# SCH_AT89.net
KiCad netlist of a schematic drawn in Altium Designer
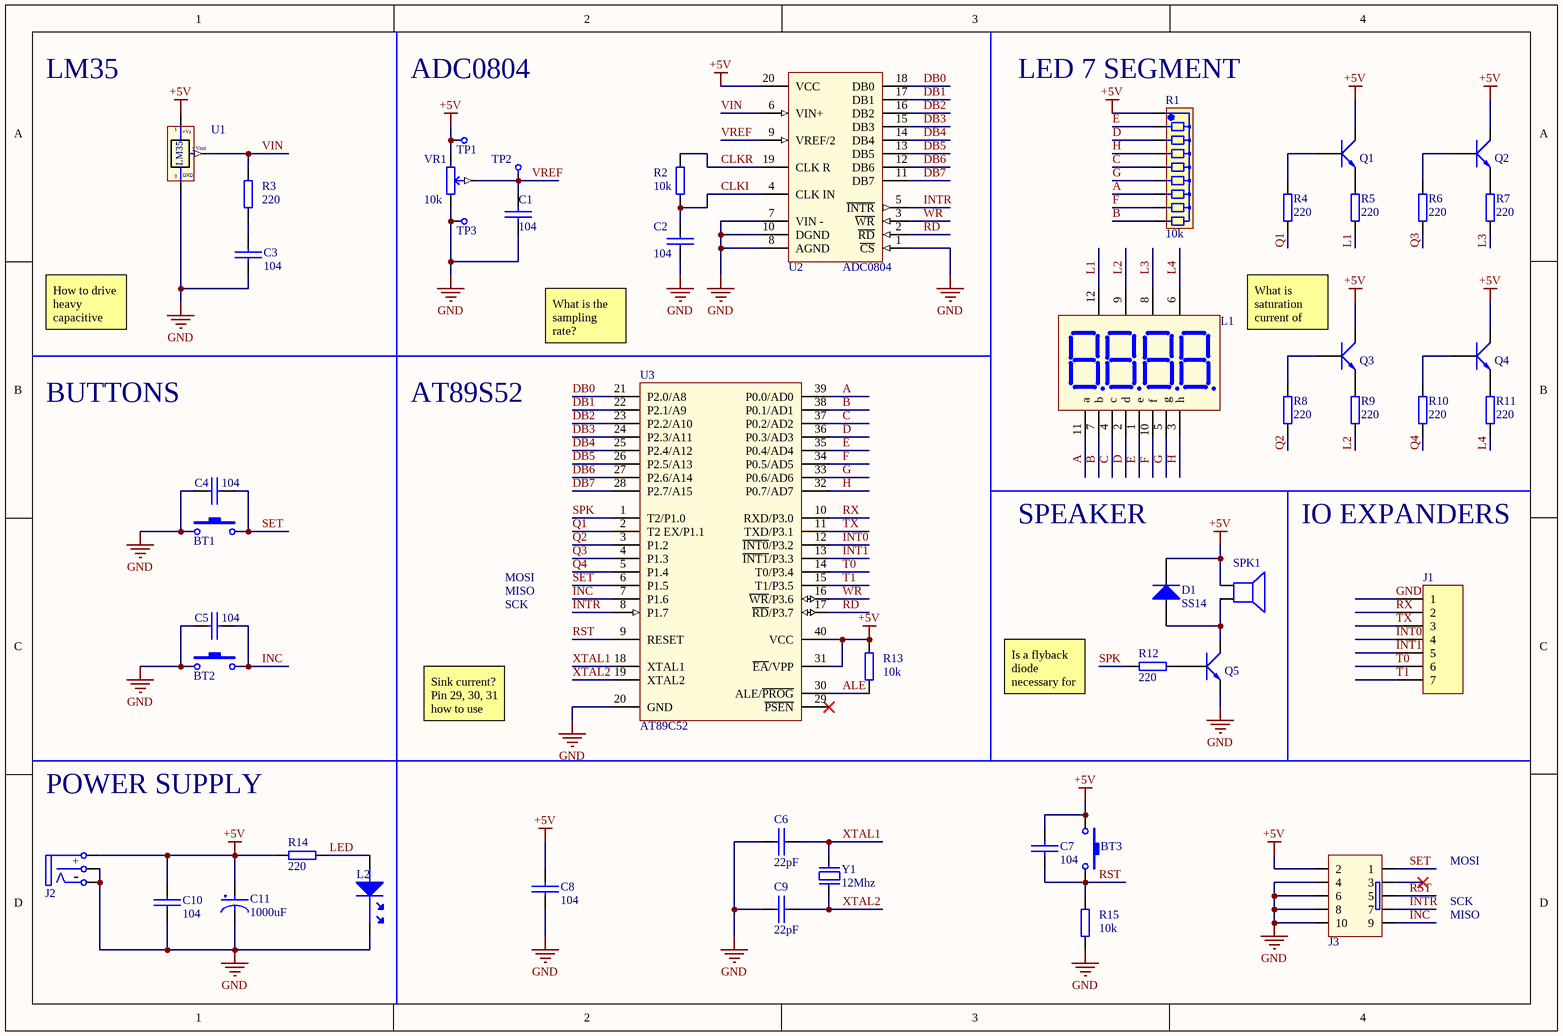
[diagram p0: SCH_AT89.SchDoc]

(export (version "E")
  (design (tool "Eeschema 10.0.6"))
  (components
    (comp (ref "BT1")
      (value "Nut Nhan 2 Chan SMD 3x6x2.5")
      (footprint "Nut Nhan 2 Chan SMD 3x6x2.5")
      (libsource (lib "Altium_Lib_by_KhueNguyenCreator") (part "Nut Nhan 2 Chan SMD 3x6x2.5"))
    )
    (comp (ref "BT2")
      (value "Nut Nhan 2 Chan SMD 3x6x2.5")
      (footprint "Nut Nhan 2 Chan SMD 3x6x2.5")
      (libsource (lib "Altium_Lib_by_KhueNguyenCreator") (part "Nut Nhan 2 Chan SMD 3x6x2.5"))
    )
    (comp (ref "BT3")
      (value "Nut Nhan 2 Chan SMD 3x6x2.5")
      (footprint "Nut Nhan 2 Chan SMD 3x6x2.5")
      (libsource (lib "Altium_Lib_by_KhueNguyenCreator") (part "Nut Nhan 2 Chan SMD 3x6x2.5"))
    )
    (comp (ref "C1")
      (value "104")
      (footprint "tu 0805")
      (description "SMD")
      (libsource (lib "PRJ_AT89") (part "CAP0805"))
    )
    (comp (ref "C2")
      (value "104")
      (footprint "tu 0805")
      (description "SMD")
      (libsource (lib "PRJ_AT89") (part "CAP0805"))
    )
    (comp (ref "C3")
      (value "104")
      (footprint "tu 0805")
      (description "SMD")
      (libsource (lib "PRJ_AT89") (part "CAP0805"))
    )
    (comp (ref "C4")
      (value "104")
      (footprint "tu 0805")
      (description "SMD")
      (libsource (lib "PRJ_AT89") (part "CAP0805"))
    )
    (comp (ref "C5")
      (value "104")
      (footprint "tu 0805")
      (description "SMD")
      (libsource (lib "PRJ_AT89") (part "CAP0805"))
    )
    (comp (ref "C6")
      (value "22pF")
      (footprint "tu 0805")
      (description "SMD")
      (libsource (lib "PRJ_AT89") (part "CAP0805"))
    )
    (comp (ref "C7")
      (value "104")
      (footprint "tu 0805")
      (description "SMD")
      (libsource (lib "PRJ_AT89") (part "CAP0805"))
    )
    (comp (ref "C8")
      (value "104")
      (footprint "tu 0805")
      (description "SMD")
      (libsource (lib "PRJ_AT89") (part "CAP0805"))
    )
    (comp (ref "C9")
      (value "22pF")
      (footprint "tu 0805")
      (description "SMD")
      (libsource (lib "PRJ_AT89") (part "CAP0805"))
    )
    (comp (ref "C10")
      (value "104")
      (footprint "tu 0805")
      (description "SMD")
      (libsource (lib "PRJ_AT89") (part "CAP0805"))
    )
    (comp (ref "C11")
      (value "1000uF")
      (footprint "tu hoa 10mm")
      (description "THT")
      (libsource (lib "PRJ_AT89") (part "CAPElectrolytic"))
    )
    (comp (ref "D1")
      (value "SS14")
      (footprint "DIODE SMA")
      (description "Dán")
      (libsource (lib "Altium_Lib_by_KhueNguyenCreator") (part "Diode SS14 ( 1N5819)"))
    )
    (comp (ref "J1")
      (value "Header 7")
      (footprint "HDR1X7")
      (description "Header, 7-Pin")
      (fields (field (name "PUBLISHER") "Altium Limited"))
      (libsource (lib "Miscellaneous Connectors") (part "Header 7"))
    )
    (comp (ref "J2")
      (value "JACK DC 5.5")
      (footprint "JACK DC 5.5")
      (description "THT")
      (libsource (lib "PRJ_AT89") (part "JACK DC 5.5"))
    )
    (comp (ref "J3")
      (value "IDC 5X2")
      (footprint "IDC10")
      (description "THT")
      (libsource (lib "PRJ_AT89") (part "ICSP 5x2"))
    )
    (comp (ref "L1")
      (value "Led 7 Segment 4 digitals")
      (footprint "LED7SEG-4-0.36")
      (description "4 digit 7 segment anot")
      (libsource (lib "BYTECH_HW_LIB_2019") (part "LED7SEG-A-0.36-4DIGIT"))
    )
    (comp (ref "L2")
      (value "LED 0805")
      (footprint "LED-0805-Red")
      (description "SMD")
      (libsource (lib "PRJ_AT89") (part "LED0805"))
    )
    (comp (ref "Q1")
      (value "HF")
      (footprint "SOT23")
      (description "NPN transistor")
      (libsource (lib "Altium_Lib_by_KhueNguyenCreator") (part "C1815 HF SMD"))
    )
    (comp (ref "Q2")
      (value "HF")
      (footprint "SOT23")
      (description "NPN transistor")
      (libsource (lib "Altium_Lib_by_KhueNguyenCreator") (part "C1815 HF SMD"))
    )
    (comp (ref "Q3")
      (value "HF")
      (footprint "SOT23")
      (description "NPN transistor")
      (libsource (lib "Altium_Lib_by_KhueNguyenCreator") (part "C1815 HF SMD"))
    )
    (comp (ref "Q4")
      (value "HF")
      (footprint "SOT23")
      (description "NPN transistor")
      (libsource (lib "Altium_Lib_by_KhueNguyenCreator") (part "C1815 HF SMD"))
    )
    (comp (ref "Q5")
      (value "HF")
      (footprint "SOT23")
      (description "NPN transistor")
      (libsource (lib "Altium_Lib_by_KhueNguyenCreator") (part "C1815 HF SMD"))
    )
    (comp (ref "R1")
      (value "10k")
      (footprint "tro bang a9")
      (description "Cắm")
      (libsource (lib "Altium_Lib_by_KhueNguyenCreator") (part "Tro Bang A9 10k"))
    )
    (comp (ref "R2")
      (value "10k")
      (footprint "tro smd 0805")
      (description "SMD")
      (libsource (lib "PRJ_AT89") (part "RES0805"))
    )
    (comp (ref "R3")
      (value "220")
      (footprint "tro smd 0805")
      (description "SMD")
      (libsource (lib "PRJ_AT89") (part "RES0805"))
    )
    (comp (ref "R4")
      (value "220")
      (footprint "tro smd 0805")
      (description "SMD")
      (libsource (lib "PRJ_AT89") (part "RES0805"))
    )
    (comp (ref "R5")
      (value "220")
      (footprint "tro smd 0805")
      (description "SMD")
      (libsource (lib "PRJ_AT89") (part "RES0805"))
    )
    (comp (ref "R6")
      (value "220")
      (footprint "tro smd 0805")
      (description "SMD")
      (libsource (lib "PRJ_AT89") (part "RES0805"))
    )
    (comp (ref "R7")
      (value "220")
      (footprint "tro smd 0805")
      (description "SMD")
      (libsource (lib "PRJ_AT89") (part "RES0805"))
    )
    (comp (ref "R8")
      (value "220")
      (footprint "tro smd 0805")
      (description "SMD")
      (libsource (lib "PRJ_AT89") (part "RES0805"))
    )
    (comp (ref "R9")
      (value "220")
      (footprint "tro smd 0805")
      (description "SMD")
      (libsource (lib "PRJ_AT89") (part "RES0805"))
    )
    (comp (ref "R10")
      (value "220")
      (footprint "tro smd 0805")
      (description "SMD")
      (libsource (lib "PRJ_AT89") (part "RES0805"))
    )
    (comp (ref "R11")
      (value "220")
      (footprint "tro smd 0805")
      (description "SMD")
      (libsource (lib "PRJ_AT89") (part "RES0805"))
    )
    (comp (ref "R12")
      (value "220")
      (footprint "tro smd 0805")
      (description "SMD")
      (libsource (lib "PRJ_AT89") (part "RES0805"))
    )
    (comp (ref "R13")
      (value "10k")
      (footprint "tro smd 0805")
      (description "SMD")
      (libsource (lib "PRJ_AT89") (part "RES0805"))
    )
    (comp (ref "R14")
      (value "220")
      (footprint "tro smd 0805")
      (description "SMD")
      (libsource (lib "PRJ_AT89") (part "RES0805"))
    )
    (comp (ref "R15")
      (value "10k")
      (footprint "tro smd 0805")
      (description "SMD")
      (libsource (lib "PRJ_AT89") (part "RES0805"))
    )
    (comp (ref "SPK1")
      (value "Speaker")
      (footprint "Coi Chip Speacker")
      (description "Còi chip")
      (libsource (lib "Altium_Lib_by_KhueNguyenCreator") (part "Coi Chip Speaker"))
    )
    (comp (ref "TP1")
      (value "TESTPOINT")
      (footprint "Testpoint")
      (description "SMD")
      (libsource (lib "PRJ_AT89") (part "TESTPOINT"))
    )
    (comp (ref "TP2")
      (value "TESTPOINT")
      (footprint "Testpoint")
      (description "SMD")
      (libsource (lib "PRJ_AT89") (part "TESTPOINT"))
    )
    (comp (ref "TP3")
      (value "TESTPOINT")
      (footprint "Testpoint")
      (description "SMD")
      (libsource (lib "PRJ_AT89") (part "TESTPOINT"))
    )
    (comp (ref "U1")
      (value "LM35")
      (footprint "QTO-92")
      (description "THT")
      (libsource (lib "PRJ_AT89") (part "LM35"))
    )
    (comp (ref "U2")
      (value "ADC0804")
      (footprint "DIP20")
      (description "THT")
      (libsource (lib "PRJ_AT89") (part "ADC0804"))
    )
    (comp (ref "U3")
      (value "AT89C52")
      (footprint "DIP40/W0.6")
      (description "THT")
      (libsource (lib "PRJ_AT89") (part "AT89C52"))
    )
    (comp (ref "VR1")
      (value "10k")
      (footprint "Bien Tro Vi Chinh Dung")
      (description "THT")
      (libsource (lib "PRJ_AT89") (part "RESVariable"))
    )
    (comp (ref "Y1")
      (value "12Mhz")
      (footprint "Thach Anh 2 chan cam")
      (description "Crystal For all Crystal 2pin.")
      (libsource (lib "Altium_Lib_by_KhueNguyenCreator") (part "Thach Anh 2 chan Cam"))
    )
  )
  (nets
    (net (code "1") (name "+5V") (class "Default")
      (node (ref "BT3") (pin "1") (pinfunction "1_1") (pintype "passive"))
      (node (ref "C10") (pin "1") (pinfunction "1_1") (pintype "passive"))
      (node (ref "C11") (pin "1") (pinfunction "1_1") (pintype "passive"))
      (node (ref "C7") (pin "1") (pinfunction "1_1") (pintype "passive"))
      (node (ref "C8") (pin "1") (pinfunction "1_1") (pintype "passive"))
      (node (ref "D1") (pin "2") (pinfunction "K_2") (pintype "passive"))
      (node (ref "J2") (pin "1") (pinfunction "T_1") (pintype "passive"))
      (node (ref "J3") (pin "2") (pinfunction "2_2") (pintype "passive"))
      (node (ref "Q1") (pin "3") (pinfunction "C_3") (pintype "passive"))
      (node (ref "Q2") (pin "3") (pinfunction "C_3") (pintype "passive"))
      (node (ref "Q3") (pin "3") (pinfunction "C_3") (pintype "passive"))
      (node (ref "Q4") (pin "3") (pinfunction "C_3") (pintype "passive"))
      (node (ref "R1") (pin "1") (pinfunction "1_1") (pintype "passive"))
      (node (ref "R13") (pin "2") (pinfunction "2_2") (pintype "passive"))
      (node (ref "R14") (pin "2") (pinfunction "2_2") (pintype "passive"))
      (node (ref "SPK1") (pin "1") (pinfunction "1_1") (pintype "passive"))
      (node (ref "TP1") (pin "1") (pinfunction "TP_1") (pintype "passive"))
      (node (ref "U1") (pin "1") (pinfunction "+Vs_1") (pintype "passive"))
      (node (ref "U2") (pin "20") (pinfunction "VCC_20") (pintype "power_in"))
      (node (ref "U3") (pin "31") (pinfunction "~{EA}/VPP_31") (pintype "passive"))
      (node (ref "U3") (pin "40") (pinfunction "VCC_40") (pintype "power_in"))
      (node (ref "VR1") (pin "1") (pinfunction "1_1") (pintype "passive"))
    )
    (net (code "2") (name "/A") (class "Default")
      (node (ref "L1") (pin "11") (pinfunction "a_11") (pintype "passive"))
      (node (ref "R1") (pin "7") (pinfunction "7_7") (pintype "passive"))
      (node (ref "U3") (pin "39") (pinfunction "P0.0/AD0_39") (pintype "passive"))
    )
    (net (code "3") (name "/ALE") (class "Default")
      (node (ref "R13") (pin "1") (pinfunction "1_1") (pintype "passive"))
      (node (ref "U3") (pin "30") (pinfunction "ALE/~{PROG}_30") (pintype "passive"))
    )
    (net (code "4") (name "/B") (class "Default")
      (node (ref "L1") (pin "7") (pinfunction "b_7") (pintype "passive"))
      (node (ref "R1") (pin "9") (pinfunction "9_9") (pintype "passive"))
      (node (ref "U3") (pin "38") (pinfunction "P0.1/AD1_38") (pintype "passive"))
    )
    (net (code "5") (name "/C") (class "Default")
      (node (ref "L1") (pin "4") (pinfunction "c_4") (pintype "passive"))
      (node (ref "R1") (pin "5") (pinfunction "5_5") (pintype "passive"))
      (node (ref "U3") (pin "37") (pinfunction "P0.2/AD2_37") (pintype "passive"))
    )
    (net (code "6") (name "/CLKI") (class "Default")
      (node (ref "C2") (pin "1") (pinfunction "1_1") (pintype "passive"))
      (node (ref "R2") (pin "1") (pinfunction "1_1") (pintype "passive"))
      (node (ref "U2") (pin "4") (pinfunction "CLK_IN_4") (pintype "passive"))
    )
    (net (code "7") (name "/CLKR") (class "Default")
      (node (ref "R2") (pin "2") (pinfunction "2_2") (pintype "passive"))
      (node (ref "U2") (pin "19") (pinfunction "CLK_R_19") (pintype "passive"))
    )
    (net (code "8") (name "/D") (class "Default")
      (node (ref "L1") (pin "2") (pinfunction "d_2") (pintype "passive"))
      (node (ref "R1") (pin "3") (pinfunction "3_3") (pintype "passive"))
      (node (ref "U3") (pin "36") (pinfunction "P0.3/AD3_36") (pintype "passive"))
    )
    (net (code "9") (name "/DB0") (class "Default")
      (node (ref "U2") (pin "18") (pinfunction "DB0_18") (pintype "tri_state"))
      (node (ref "U3") (pin "21") (pinfunction "P2.0/A8_21") (pintype "passive"))
    )
    (net (code "10") (name "/DB1") (class "Default")
      (node (ref "U2") (pin "17") (pinfunction "DB1_17") (pintype "tri_state"))
      (node (ref "U3") (pin "22") (pinfunction "P2.1/A9_22") (pintype "passive"))
    )
    (net (code "11") (name "/DB2") (class "Default")
      (node (ref "U2") (pin "16") (pinfunction "DB2_16") (pintype "tri_state"))
      (node (ref "U3") (pin "23") (pinfunction "P2.2/A10_23") (pintype "passive"))
    )
    (net (code "12") (name "/DB3") (class "Default")
      (node (ref "U2") (pin "15") (pinfunction "DB3_15") (pintype "tri_state"))
      (node (ref "U3") (pin "24") (pinfunction "P2.3/A11_24") (pintype "passive"))
    )
    (net (code "13") (name "/DB4") (class "Default")
      (node (ref "U2") (pin "14") (pinfunction "DB4_14") (pintype "tri_state"))
      (node (ref "U3") (pin "25") (pinfunction "P2.4/A12_25") (pintype "passive"))
    )
    (net (code "14") (name "/DB5") (class "Default")
      (node (ref "U2") (pin "13") (pinfunction "DB5_13") (pintype "tri_state"))
      (node (ref "U3") (pin "26") (pinfunction "P2.5/A13_26") (pintype "passive"))
    )
    (net (code "15") (name "/DB6") (class "Default")
      (node (ref "U2") (pin "12") (pinfunction "DB6_12") (pintype "tri_state"))
      (node (ref "U3") (pin "27") (pinfunction "P2.6/A14_27") (pintype "passive"))
    )
    (net (code "16") (name "/DB7") (class "Default")
      (node (ref "U2") (pin "11") (pinfunction "DB7_11") (pintype "tri_state"))
      (node (ref "U3") (pin "28") (pinfunction "P2.7/A15_28") (pintype "passive"))
    )
    (net (code "17") (name "/E") (class "Default")
      (node (ref "L1") (pin "1") (pinfunction "e_1") (pintype "passive"))
      (node (ref "R1") (pin "2") (pinfunction "2_2") (pintype "passive"))
      (node (ref "U3") (pin "35") (pinfunction "P0.4/AD4_35") (pintype "passive"))
    )
    (net (code "18") (name "/F") (class "Default")
      (node (ref "L1") (pin "10") (pinfunction "f_10") (pintype "passive"))
      (node (ref "R1") (pin "8") (pinfunction "8_8") (pintype "passive"))
      (node (ref "U3") (pin "34") (pinfunction "P0.5/AD5_34") (pintype "passive"))
    )
    (net (code "19") (name "/G") (class "Default")
      (node (ref "L1") (pin "5") (pinfunction "g_5") (pintype "passive"))
      (node (ref "R1") (pin "6") (pinfunction "6_6") (pintype "passive"))
      (node (ref "U3") (pin "33") (pinfunction "P0.6/AD6_33") (pintype "passive"))
    )
    (net (code "20") (name "/H") (class "Default")
      (node (ref "L1") (pin "3") (pinfunction "h_3") (pintype "passive"))
      (node (ref "R1") (pin "4") (pinfunction "4_4") (pintype "passive"))
      (node (ref "U3") (pin "32") (pinfunction "P0.7/AD7_32") (pintype "passive"))
    )
    (net (code "21") (name "/INC") (class "Default")
      (node (ref "BT2") (pin "1") (pinfunction "1_1") (pintype "passive"))
      (node (ref "C5") (pin "1") (pinfunction "1_1") (pintype "passive"))
      (node (ref "J3") (pin "9") (pinfunction "9_9") (pintype "passive"))
      (node (ref "U3") (pin "7") (pinfunction "P1.6_7") (pintype "passive"))
    )
    (net (code "22") (name "/INT0") (class "Default")
      (node (ref "J1") (pin "4") (pinfunction "4_4") (pintype "passive"))
      (node (ref "U3") (pin "12") (pinfunction "~{INT0}/P3.2_12") (pintype "passive"))
    )
    (net (code "23") (name "/INT1") (class "Default")
      (node (ref "J1") (pin "5") (pinfunction "5_5") (pintype "passive"))
      (node (ref "U3") (pin "13") (pinfunction "~{INT1}/P3.3_13") (pintype "passive"))
    )
    (net (code "24") (name "/INTR") (class "Default")
      (node (ref "J3") (pin "7") (pinfunction "7_7") (pintype "passive"))
      (node (ref "U2") (pin "5") (pinfunction "~{INTR}_5") (pintype "output"))
      (node (ref "U3") (pin "8") (pinfunction "P1.7_8") (pintype "input"))
    )
    (net (code "25") (name "/L1") (class "Default")
      (node (ref "L1") (pin "12") (pinfunction "V1_12") (pintype "passive"))
      (node (ref "R5") (pin "2") (pinfunction "2_2") (pintype "passive"))
    )
    (net (code "26") (name "/L2") (class "Default")
      (node (ref "L1") (pin "9") (pinfunction "V2_9") (pintype "passive"))
      (node (ref "R9") (pin "2") (pinfunction "2_2") (pintype "passive"))
    )
    (net (code "27") (name "/L3") (class "Default")
      (node (ref "L1") (pin "8") (pinfunction "V3_8") (pintype "passive"))
      (node (ref "R7") (pin "2") (pinfunction "2_2") (pintype "passive"))
    )
    (net (code "28") (name "/L4") (class "Default")
      (node (ref "L1") (pin "6") (pinfunction "V4_6") (pintype "passive"))
      (node (ref "R11") (pin "2") (pinfunction "2_2") (pintype "passive"))
    )
    (net (code "29") (name "/LED") (class "Default")
      (node (ref "L2") (pin "2") (pinfunction "K_2") (pintype "passive"))
      (node (ref "R14") (pin "1") (pinfunction "1_1") (pintype "passive"))
    )
    (net (code "30") (name "/Q1") (class "Default")
      (node (ref "R4") (pin "2") (pinfunction "2_2") (pintype "passive"))
      (node (ref "U3") (pin "2") (pinfunction "T2_EX/P1.1_2") (pintype "passive"))
    )
    (net (code "31") (name "/Q2") (class "Default")
      (node (ref "R8") (pin "2") (pinfunction "2_2") (pintype "passive"))
      (node (ref "U3") (pin "3") (pinfunction "P1.2_3") (pintype "passive"))
    )
    (net (code "32") (name "/Q3") (class "Default")
      (node (ref "R6") (pin "2") (pinfunction "2_2") (pintype "passive"))
      (node (ref "U3") (pin "4") (pinfunction "P1.3_4") (pintype "passive"))
    )
    (net (code "33") (name "/Q4") (class "Default")
      (node (ref "R10") (pin "2") (pinfunction "2_2") (pintype "passive"))
      (node (ref "U3") (pin "5") (pinfunction "P1.4_5") (pintype "passive"))
    )
    (net (code "34") (name "/RD") (class "Default")
      (node (ref "U2") (pin "2") (pinfunction "~{RD}_2") (pintype "input"))
      (node (ref "U3") (pin "17") (pinfunction "~{RD}/P3.7_17") (pintype "bidirectional"))
    )
    (net (code "35") (name "/RST") (class "Default")
      (node (ref "BT3") (pin "2") (pinfunction "2_2") (pintype "passive"))
      (node (ref "C7") (pin "2") (pinfunction "2_2") (pintype "passive"))
      (node (ref "J3") (pin "5") (pinfunction "5_5") (pintype "passive"))
      (node (ref "R15") (pin "2") (pinfunction "2_2") (pintype "passive"))
      (node (ref "U3") (pin "9") (pinfunction "RESET_9") (pintype "passive"))
    )
    (net (code "36") (name "/RX") (class "Default")
      (node (ref "J1") (pin "2") (pinfunction "2_2") (pintype "passive"))
      (node (ref "U3") (pin "10") (pinfunction "RXD/P3.0_10") (pintype "passive"))
    )
    (net (code "37") (name "/SET") (class "Default")
      (node (ref "BT1") (pin "1") (pinfunction "1_1") (pintype "passive"))
      (node (ref "C4") (pin "1") (pinfunction "1_1") (pintype "passive"))
      (node (ref "J3") (pin "1") (pinfunction "1_1") (pintype "passive"))
      (node (ref "U3") (pin "6") (pinfunction "P1.5_6") (pintype "passive"))
    )
    (net (code "38") (name "/SPK") (class "Default")
      (node (ref "R12") (pin "2") (pinfunction "2_2") (pintype "passive"))
      (node (ref "U3") (pin "1") (pinfunction "T2/P1.0_1") (pintype "passive"))
    )
    (net (code "39") (name "/T0") (class "Default")
      (node (ref "J1") (pin "6") (pinfunction "6_6") (pintype "passive"))
      (node (ref "U3") (pin "14") (pinfunction "T0/P3.4_14") (pintype "passive"))
    )
    (net (code "40") (name "/T1") (class "Default")
      (node (ref "J1") (pin "7") (pinfunction "7_7") (pintype "passive"))
      (node (ref "U3") (pin "15") (pinfunction "T1/P3.5_15") (pintype "passive"))
    )
    (net (code "41") (name "/TX") (class "Default")
      (node (ref "J1") (pin "3") (pinfunction "3_3") (pintype "passive"))
      (node (ref "U3") (pin "11") (pinfunction "TXD/P3.1_11") (pintype "passive"))
    )
    (net (code "42") (name "/VIN") (class "Default")
      (node (ref "R3") (pin "2") (pinfunction "2_2") (pintype "passive"))
      (node (ref "U1") (pin "2") (pinfunction "Vout_2") (pintype "output"))
      (node (ref "U2") (pin "6") (pinfunction "VIN+_6") (pintype "input"))
    )
    (net (code "43") (name "/VREF") (class "Default")
      (node (ref "C1") (pin "1") (pinfunction "1_1") (pintype "passive"))
      (node (ref "TP2") (pin "1") (pinfunction "TP_1") (pintype "passive"))
      (node (ref "U2") (pin "9") (pinfunction "VREF/2_9") (pintype "input"))
      (node (ref "VR1") (pin "2") (pinfunction "2_2") (pintype "output"))
    )
    (net (code "44") (name "/WR") (class "Default")
      (node (ref "U2") (pin "3") (pinfunction "~{WR}_3") (pintype "input"))
      (node (ref "U3") (pin "16") (pinfunction "~{WR}/P3.6_16") (pintype "bidirectional"))
    )
    (net (code "45") (name "/XTAL1") (class "Default")
      (node (ref "C6") (pin "1") (pinfunction "1_1") (pintype "passive"))
      (node (ref "U3") (pin "18") (pinfunction "XTAL1_18") (pintype "passive"))
      (node (ref "Y1") (pin "2") (pinfunction "2_2") (pintype "passive"))
    )
    (net (code "46") (name "/XTAL2") (class "Default")
      (node (ref "C9") (pin "1") (pinfunction "1_1") (pintype "passive"))
      (node (ref "U3") (pin "19") (pinfunction "XTAL2_19") (pintype "passive"))
      (node (ref "Y1") (pin "1") (pinfunction "1_1") (pintype "passive"))
    )
    (net (code "47") (name "GND") (class "Default")
      (node (ref "BT1") (pin "2") (pinfunction "2_2") (pintype "passive"))
      (node (ref "BT2") (pin "2") (pinfunction "2_2") (pintype "passive"))
      (node (ref "C1") (pin "2") (pinfunction "2_2") (pintype "passive"))
      (node (ref "C10") (pin "2") (pinfunction "2_2") (pintype "passive"))
      (node (ref "C11") (pin "2") (pinfunction "2_2") (pintype "passive"))
      (node (ref "C2") (pin "2") (pinfunction "2_2") (pintype "passive"))
      (node (ref "C3") (pin "2") (pinfunction "2_2") (pintype "passive"))
      (node (ref "C4") (pin "2") (pinfunction "2_2") (pintype "passive"))
      (node (ref "C5") (pin "2") (pinfunction "2_2") (pintype "passive"))
      (node (ref "C6") (pin "2") (pinfunction "2_2") (pintype "passive"))
      (node (ref "C8") (pin "2") (pinfunction "2_2") (pintype "passive"))
      (node (ref "C9") (pin "2") (pinfunction "2_2") (pintype "passive"))
      (node (ref "J1") (pin "1") (pinfunction "1_1") (pintype "passive"))
      (node (ref "J2") (pin "2") (pinfunction "TN_2") (pintype "passive"))
      (node (ref "J2") (pin "3") (pinfunction "S_3") (pintype "power_in"))
      (node (ref "J3") (pin "10") (pinfunction "10_10") (pintype "passive"))
      (node (ref "J3") (pin "4") (pinfunction "4_4") (pintype "passive"))
      (node (ref "J3") (pin "6") (pinfunction "6_6") (pintype "passive"))
      (node (ref "J3") (pin "8") (pinfunction "8_8") (pintype "passive"))
      (node (ref "L2") (pin "1") (pinfunction "A_1") (pintype "passive"))
      (node (ref "Q5") (pin "2") (pinfunction "E_2") (pintype "passive"))
      (node (ref "R15") (pin "1") (pinfunction "1_1") (pintype "passive"))
      (node (ref "TP3") (pin "1") (pinfunction "TP_1") (pintype "passive"))
      (node (ref "U1") (pin "3") (pinfunction "-_3") (pintype "passive"))
      (node (ref "U2") (pin "1") (pinfunction "~{CS}_1") (pintype "input"))
      (node (ref "U2") (pin "10") (pinfunction "DGND_10") (pintype "power_in"))
      (node (ref "U2") (pin "7") (pinfunction "VIN_-_7") (pintype "passive"))
      (node (ref "U2") (pin "8") (pinfunction "AGND_8") (pintype "power_in"))
      (node (ref "U3") (pin "20") (pinfunction "GND_20") (pintype "passive"))
      (node (ref "VR1") (pin "3") (pinfunction "3_3") (pintype "passive"))
    )
    (net (code "48") (name "Net-(C3-Pad1)") (class "Default")
      (node (ref "C3") (pin "1") (pinfunction "1_1") (pintype "passive"))
      (node (ref "R3") (pin "1") (pinfunction "1_1") (pintype "passive"))
    )
    (net (code "49") (name "Net-(D1-A)") (class "Default")
      (node (ref "D1") (pin "1") (pinfunction "A_1") (pintype "passive"))
      (node (ref "Q5") (pin "3") (pinfunction "C_3") (pintype "passive"))
      (node (ref "SPK1") (pin "2") (pinfunction "2_2") (pintype "passive"))
    )
    (net (code "50") (name "Net-(Q1-B)") (class "Default")
      (node (ref "Q1") (pin "1") (pinfunction "B_1") (pintype "passive"))
      (node (ref "R4") (pin "1") (pinfunction "1_1") (pintype "passive"))
    )
    (net (code "51") (name "Net-(Q1-E)") (class "Default")
      (node (ref "Q1") (pin "2") (pinfunction "E_2") (pintype "passive"))
      (node (ref "R5") (pin "1") (pinfunction "1_1") (pintype "passive"))
    )
    (net (code "52") (name "Net-(Q2-B)") (class "Default")
      (node (ref "Q2") (pin "1") (pinfunction "B_1") (pintype "passive"))
      (node (ref "R6") (pin "1") (pinfunction "1_1") (pintype "passive"))
    )
    (net (code "53") (name "Net-(Q2-E)") (class "Default")
      (node (ref "Q2") (pin "2") (pinfunction "E_2") (pintype "passive"))
      (node (ref "R7") (pin "1") (pinfunction "1_1") (pintype "passive"))
    )
    (net (code "54") (name "Net-(Q3-B)") (class "Default")
      (node (ref "Q3") (pin "1") (pinfunction "B_1") (pintype "passive"))
      (node (ref "R8") (pin "1") (pinfunction "1_1") (pintype "passive"))
    )
    (net (code "55") (name "Net-(Q3-E)") (class "Default")
      (node (ref "Q3") (pin "2") (pinfunction "E_2") (pintype "passive"))
      (node (ref "R9") (pin "1") (pinfunction "1_1") (pintype "passive"))
    )
    (net (code "56") (name "Net-(Q4-B)") (class "Default")
      (node (ref "Q4") (pin "1") (pinfunction "B_1") (pintype "passive"))
      (node (ref "R10") (pin "1") (pinfunction "1_1") (pintype "passive"))
    )
    (net (code "57") (name "Net-(Q4-E)") (class "Default")
      (node (ref "Q4") (pin "2") (pinfunction "E_2") (pintype "passive"))
      (node (ref "R11") (pin "1") (pinfunction "1_1") (pintype "passive"))
    )
    (net (code "58") (name "Net-(Q5-B)") (class "Default")
      (node (ref "Q5") (pin "1") (pinfunction "B_1") (pintype "passive"))
      (node (ref "R12") (pin "1") (pinfunction "1_1") (pintype "passive"))
    )
    (net (code "59") (name "unconnected-(J3-Pad3)") (class "Default")
      (node (ref "J3") (pin "3") (pinfunction "3_3") (pintype "passive+no_connect"))
    )
    (net (code "60") (name "unconnected-(U3-~{PSEN}-Pad29)") (class "Default")
      (node (ref "U3") (pin "29") (pinfunction "~{PSEN}_29") (pintype "passive+no_connect"))
    )
  )
)
